# CW308T_MSP430FR5_micro.net
KiCad netlist of a schematic drawn in Altium Designer
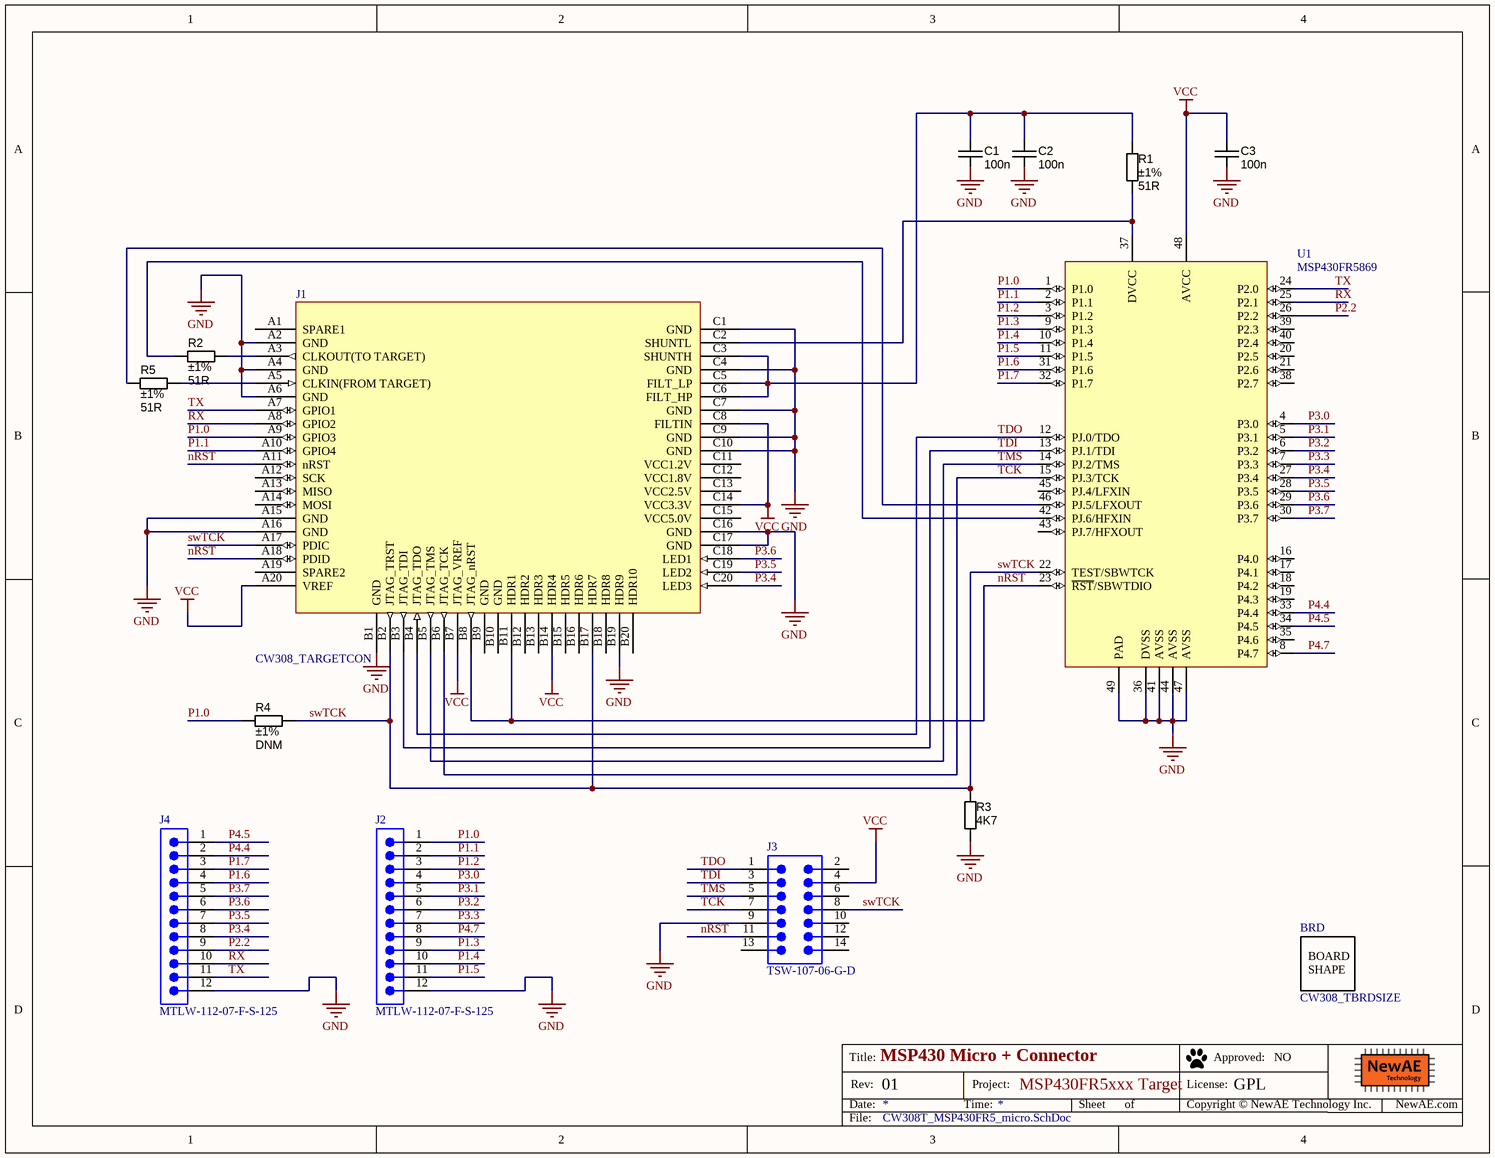
[diagram p0: CW308T_MSP430FR5_micro.SchDoc]

(export (version "E")
  (design (tool "Eeschema 10.0.6"))
  (components
    (comp (ref "BRD")
      (value "CW308_TBRDSIZE")
      (footprint "CW308T_TBOARD_DEFSIZE")
      (description "308T Board Outline (Layer 1)")
      (fields (field (name "PART NUMBER") "CW308T_BRDSHAPE_DEFAULT"))
      (libsource (lib "NewAE_AltiumLib") (part "CW308_TBRDSIZE"))
    )
    (comp (ref "C1")
      (value "100n")
      (footprint "CAPC1608X90N")
      (description "Capacitor SMD Cer 100nF 10% 50V X7R 0603")
      (fields (field (name "TOLERANCE") "±10%") (field (name "Comment") "approved sub OK"))
      (libsource (lib "PBL - Capacitors") (part "CAPC_100n_0603_X7R_50V_10%"))
    )
    (comp (ref "C2")
      (value "100n")
      (footprint "CAPC1608X90N")
      (description "Capacitor SMD Cer 100nF 10% 50V X7R 0603")
      (fields (field (name "TOLERANCE") "±10%") (field (name "Comment") "approved sub OK"))
      (libsource (lib "PBL - Capacitors") (part "CAPC_100n_0603_X7R_50V_10%"))
    )
    (comp (ref "C3")
      (value "100n")
      (footprint "CAPC1608X90N")
      (description "Capacitor SMD Cer 100nF 10% 50V X7R 0603")
      (fields (field (name "TOLERANCE") "±10%") (field (name "Comment") "approved sub OK"))
      (libsource (lib "PBL - Capacitors") (part "CAPC_100n_0603_X7R_50V_10%"))
    )
    (comp (ref "J1")
      (value "CW308_TARGETCON")
      (footprint "ChipWhisperer_AltiumLib:CW308_TBOARD_CONN")
      (description "CW308 \"Standard\" Target Board Connector")
      (libsource (lib "ChipWhisperer_AltiumLib") (part "CW308_TBOARD"))
    )
    (comp (ref "J2")
      (value "MTLW-112-07-F-S-125")
      (footprint "SMTC-MTLW-112-07-X-S-125")
      (fields (field (name "MANUFACTURER") "Samtec"))
      (libsource (lib "Altium Content Vault") (part "SMTC-MTLW-112-07-X-S-125"))
    )
    (comp (ref "J3")
      (value "TSW-107-06-G-D")
      (footprint "SMTC-TSW-107-06-X-D")
      (fields (field (name "MANUFACTURER") "Samtec"))
      (libsource (lib "Altium Content Vault") (part "SMTC-TSW-107-X-X-D-X"))
    )
    (comp (ref "J4")
      (value "MTLW-112-07-F-S-125")
      (footprint "SMTC-MTLW-112-07-X-S-125")
      (fields (field (name "MANUFACTURER") "Samtec"))
      (libsource (lib "Altium Content Vault") (part "SMTC-MTLW-112-07-X-S-125"))
    )
    (comp (ref "R1")
      (value "51R")
      (footprint "RESC1608X55N")
      (description "Resistor SMD chip 51 Ohm 0.1W 1% 0603")
      (fields (field (name "TOLERANCE") "±1%") (field (name "Comment") "Thick Film"))
      (libsource (lib "PBL - Resistors") (part "RES_51R_0603_1%"))
    )
    (comp (ref "R2")
      (value "51R")
      (footprint "RESC1608X55N")
      (description "Resistor SMD chip 51 Ohm 0.1W 1% 0603")
      (fields (field (name "TOLERANCE") "±1%") (field (name "Comment") "Thick Film"))
      (libsource (lib "") (part "RES_51R_0603_1%_1"))
    )
    (comp (ref "R3")
      (value "4K7")
      (footprint "RESC1608X55N")
      (description "Resistor SMD chip 4.7k Ohm 0.1W 5% 0603")
      (fields (field (name "TOLERANCE") "±5%") (field (name "Comment") "Thick Film"))
      (libsource (lib "PBL - Resistors") (part "RES_4K7_0603_5%"))
    )
    (comp (ref "R4")
      (value "DNM")
      (footprint "RESC1608X55N")
      (description "Resistor SMD chip 51 Ohm 0.1W 1% 0603")
      (fields (field (name "TOLERANCE") "±1%") (field (name "Comment") "Thick Film"))
      (libsource (lib "") (part "RES_51R_0603_1%_1"))
    )
    (comp (ref "R5")
      (value "51R")
      (footprint "RESC1608X55N")
      (description "Resistor SMD chip 51 Ohm 0.1W 1% 0603")
      (fields (field (name "TOLERANCE") "±1%") (field (name "Comment") "Thick Film"))
      (libsource (lib "") (part "RES_51R_0603_1%_1"))
    )
    (comp (ref "U1")
      (value "MSP430FR5869")
      (footprint "NewAE_AltiumLib:QFN50P700X700X100_HS-49M")
      (description "MSP430, 16-bit MCU, FR sram")
      (libsource (lib "NewAE_AltiumLib") (part "MSP430FR869"))
    )
  )
  (nets
    (net (code "1") (name "/P1.0") (class "Default")
      (node (ref "J1") (pin "A9") (pinfunction "GPIO3_A9") (pintype "bidirectional"))
      (node (ref "J2") (pin "1") (pinfunction "1_1") (pintype "passive"))
      (node (ref "R4") (pin "1") (pinfunction "1_1") (pintype "passive"))
      (node (ref "U1") (pin "1") (pinfunction "P1.0_1") (pintype "bidirectional"))
    )
    (net (code "2") (name "/P1.1") (class "Default")
      (node (ref "J1") (pin "A10") (pinfunction "GPIO4_A10") (pintype "bidirectional"))
      (node (ref "J2") (pin "2") (pinfunction "2_2") (pintype "passive"))
      (node (ref "U1") (pin "2") (pinfunction "P1.1_2") (pintype "bidirectional"))
    )
    (net (code "3") (name "/P1.2") (class "Default")
      (node (ref "J2") (pin "3") (pinfunction "3_3") (pintype "passive"))
      (node (ref "U1") (pin "3") (pinfunction "P1.2_3") (pintype "bidirectional"))
    )
    (net (code "4") (name "/P1.3") (class "Default")
      (node (ref "J2") (pin "9") (pinfunction "9_9") (pintype "passive"))
      (node (ref "U1") (pin "9") (pinfunction "P1.3_9") (pintype "bidirectional"))
    )
    (net (code "5") (name "/P1.4") (class "Default")
      (node (ref "J2") (pin "10") (pinfunction "10_10") (pintype "passive"))
      (node (ref "U1") (pin "10") (pinfunction "P1.4_10") (pintype "bidirectional"))
    )
    (net (code "6") (name "/P1.5") (class "Default")
      (node (ref "J2") (pin "11") (pinfunction "11_11") (pintype "passive"))
      (node (ref "U1") (pin "11") (pinfunction "P1.5_11") (pintype "bidirectional"))
    )
    (net (code "7") (name "/P1.6") (class "Default")
      (node (ref "J4") (pin "4") (pinfunction "4_4") (pintype "passive"))
      (node (ref "U1") (pin "31") (pinfunction "P1.6_31") (pintype "bidirectional"))
    )
    (net (code "8") (name "/P1.7") (class "Default")
      (node (ref "J4") (pin "3") (pinfunction "3_3") (pintype "passive"))
      (node (ref "U1") (pin "32") (pinfunction "P1.7_32") (pintype "bidirectional"))
    )
    (net (code "9") (name "/P2.2") (class "Default")
      (node (ref "J4") (pin "9") (pinfunction "9_9") (pintype "passive"))
      (node (ref "U1") (pin "26") (pinfunction "P2.2_26") (pintype "bidirectional"))
    )
    (net (code "10") (name "/P3.0") (class "Default")
      (node (ref "J2") (pin "4") (pinfunction "4_4") (pintype "passive"))
      (node (ref "U1") (pin "4") (pinfunction "P3.0_4") (pintype "bidirectional"))
    )
    (net (code "11") (name "/P3.1") (class "Default")
      (node (ref "J2") (pin "5") (pinfunction "5_5") (pintype "passive"))
      (node (ref "U1") (pin "5") (pinfunction "P3.1_5") (pintype "bidirectional"))
    )
    (net (code "12") (name "/P3.2") (class "Default")
      (node (ref "J2") (pin "6") (pinfunction "6_6") (pintype "passive"))
      (node (ref "U1") (pin "6") (pinfunction "P3.2_6") (pintype "bidirectional"))
    )
    (net (code "13") (name "/P3.3") (class "Default")
      (node (ref "J2") (pin "7") (pinfunction "7_7") (pintype "passive"))
      (node (ref "U1") (pin "7") (pinfunction "P3.3_7") (pintype "bidirectional"))
    )
    (net (code "14") (name "/P3.4") (class "Default")
      (node (ref "J1") (pin "C20") (pinfunction "LED3_C20") (pintype "input"))
      (node (ref "J4") (pin "8") (pinfunction "8_8") (pintype "passive"))
      (node (ref "U1") (pin "27") (pinfunction "P3.4_27") (pintype "bidirectional"))
    )
    (net (code "15") (name "/P3.5") (class "Default")
      (node (ref "J1") (pin "C19") (pinfunction "LED2_C19") (pintype "input"))
      (node (ref "J4") (pin "7") (pinfunction "7_7") (pintype "passive"))
      (node (ref "U1") (pin "28") (pinfunction "P3.5_28") (pintype "bidirectional"))
    )
    (net (code "16") (name "/P3.6") (class "Default")
      (node (ref "J1") (pin "C18") (pinfunction "LED1_C18") (pintype "input"))
      (node (ref "J4") (pin "6") (pinfunction "6_6") (pintype "passive"))
      (node (ref "U1") (pin "29") (pinfunction "P3.6_29") (pintype "bidirectional"))
    )
    (net (code "17") (name "/P3.7") (class "Default")
      (node (ref "J4") (pin "5") (pinfunction "5_5") (pintype "passive"))
      (node (ref "U1") (pin "30") (pinfunction "P3.7_30") (pintype "bidirectional"))
    )
    (net (code "18") (name "/P4.4") (class "Default")
      (node (ref "J4") (pin "2") (pinfunction "2_2") (pintype "passive"))
      (node (ref "U1") (pin "33") (pinfunction "P4.4_33") (pintype "bidirectional"))
    )
    (net (code "19") (name "/P4.5") (class "Default")
      (node (ref "J4") (pin "1") (pinfunction "1_1") (pintype "passive"))
      (node (ref "U1") (pin "34") (pinfunction "P4.5_34") (pintype "bidirectional"))
    )
    (net (code "20") (name "/P4.7") (class "Default")
      (node (ref "J2") (pin "8") (pinfunction "8_8") (pintype "passive"))
      (node (ref "U1") (pin "8") (pinfunction "P4.7_8") (pintype "bidirectional"))
    )
    (net (code "21") (name "/RX") (class "Default")
      (node (ref "J1") (pin "A8") (pinfunction "GPIO2_A8") (pintype "bidirectional"))
      (node (ref "J4") (pin "10") (pinfunction "10_10") (pintype "passive"))
      (node (ref "U1") (pin "25") (pinfunction "P2.1_25") (pintype "bidirectional"))
    )
    (net (code "22") (name "/TCK") (class "Default")
      (node (ref "J1") (pin "B6") (pinfunction "JTAG_TCK_B6") (pintype "output"))
      (node (ref "J3") (pin "7") (pinfunction "7_7") (pintype "passive"))
      (node (ref "U1") (pin "15") (pinfunction "PJ.3/TCK_15") (pintype "bidirectional"))
    )
    (net (code "23") (name "/TDI") (class "Default")
      (node (ref "J1") (pin "B3") (pinfunction "JTAG_TDI_B3") (pintype "output"))
      (node (ref "J3") (pin "3") (pinfunction "3_3") (pintype "passive"))
      (node (ref "U1") (pin "13") (pinfunction "PJ.1/TDI_13") (pintype "bidirectional"))
    )
    (net (code "24") (name "/TDO") (class "Default")
      (node (ref "J1") (pin "B4") (pinfunction "JTAG_TDO_B4") (pintype "input"))
      (node (ref "J3") (pin "1") (pinfunction "1_1") (pintype "passive"))
      (node (ref "U1") (pin "12") (pinfunction "PJ.0/TDO_12") (pintype "bidirectional"))
    )
    (net (code "25") (name "/TMS") (class "Default")
      (node (ref "J1") (pin "B5") (pinfunction "JTAG_TMS_B5") (pintype "output"))
      (node (ref "J3") (pin "5") (pinfunction "5_5") (pintype "passive"))
      (node (ref "U1") (pin "14") (pinfunction "PJ.2/TMS_14") (pintype "bidirectional"))
    )
    (net (code "26") (name "/TX") (class "Default")
      (node (ref "J1") (pin "A7") (pinfunction "GPIO1_A7") (pintype "bidirectional"))
      (node (ref "J4") (pin "11") (pinfunction "11_11") (pintype "passive"))
      (node (ref "U1") (pin "24") (pinfunction "P2.0_24") (pintype "bidirectional"))
    )
    (net (code "27") (name "/nRST") (class "Default")
      (node (ref "J1") (pin "A11") (pinfunction "nRST_A11") (pintype "bidirectional"))
      (node (ref "J1") (pin "A18") (pinfunction "PDID_A18") (pintype "bidirectional"))
      (node (ref "J1") (pin "B11") (pinfunction "HDR1_B11") (pintype "passive"))
      (node (ref "J1") (pin "B8") (pinfunction "JTAG_nRST_B8") (pintype "output"))
      (node (ref "J3") (pin "11") (pinfunction "11_11") (pintype "passive"))
      (node (ref "U1") (pin "23") (pinfunction "~{RST}/SBWTDIO_23") (pintype "bidirectional"))
    )
    (net (code "28") (name "/swTCK") (class "Default")
      (node (ref "J1") (pin "A17") (pinfunction "PDIC_A17") (pintype "bidirectional"))
      (node (ref "J1") (pin "B17") (pinfunction "HDR7_B17") (pintype "passive"))
      (node (ref "J1") (pin "B2") (pinfunction "JTAG_TRST_B2") (pintype "output"))
      (node (ref "J3") (pin "8") (pinfunction "8_8") (pintype "passive"))
      (node (ref "R3") (pin "1") (pinfunction "1_1") (pintype "passive"))
      (node (ref "R4") (pin "2") (pinfunction "2_2") (pintype "passive"))
      (node (ref "U1") (pin "22") (pinfunction "TEST/SBWTCK_22") (pintype "bidirectional"))
    )
    (net (code "29") (name "GND") (class "Default")
      (node (ref "C1") (pin "2") (pintype "passive"))
      (node (ref "C2") (pin "2") (pintype "passive"))
      (node (ref "C3") (pin "2") (pintype "passive"))
      (node (ref "J1") (pin "A15") (pinfunction "GND_A15") (pintype "passive"))
      (node (ref "J1") (pin "A16") (pinfunction "GND_A16") (pintype "passive"))
      (node (ref "J1") (pin "A2") (pinfunction "GND_A2") (pintype "passive"))
      (node (ref "J1") (pin "A4") (pinfunction "GND_A4") (pintype "passive"))
      (node (ref "J1") (pin "A6") (pinfunction "GND_A6") (pintype "power_in"))
      (node (ref "J1") (pin "B1") (pinfunction "GND_B1") (pintype "passive"))
      (node (ref "J1") (pin "B19") (pinfunction "HDR9_B19") (pintype "passive"))
      (node (ref "J1") (pin "C1") (pinfunction "GND_C1") (pintype "power_in"))
      (node (ref "J1") (pin "C10") (pinfunction "GND_C10") (pintype "power_in"))
      (node (ref "J1") (pin "C16") (pinfunction "GND_C16") (pintype "power_in"))
      (node (ref "J1") (pin "C17") (pinfunction "GND_C17") (pintype "power_in"))
      (node (ref "J1") (pin "C4") (pinfunction "GND_C4") (pintype "power_in"))
      (node (ref "J1") (pin "C7") (pinfunction "GND_C7") (pintype "power_in"))
      (node (ref "J1") (pin "C9") (pinfunction "GND_C9") (pintype "power_in"))
      (node (ref "J2") (pin "12") (pinfunction "12_12") (pintype "passive"))
      (node (ref "J3") (pin "9") (pinfunction "9_9") (pintype "passive"))
      (node (ref "J4") (pin "12") (pinfunction "12_12") (pintype "passive"))
      (node (ref "R3") (pin "2") (pinfunction "2_2") (pintype "passive"))
      (node (ref "U1") (pin "36") (pinfunction "DVSS_36") (pintype "power_in"))
      (node (ref "U1") (pin "41") (pinfunction "AVSS_41") (pintype "power_in"))
      (node (ref "U1") (pin "44") (pinfunction "AVSS_44") (pintype "power_in"))
      (node (ref "U1") (pin "47") (pinfunction "AVSS_47") (pintype "power_in"))
      (node (ref "U1") (pin "49") (pinfunction "PAD_49") (pintype "power_in"))
    )
    (net (code "30") (name "Net-(J1-CLKIN(FROM_TARGET))") (class "Default")
      (node (ref "J1") (pin "A5") (pinfunction "CLKIN(FROM_TARGET)_A5") (pintype "input"))
      (node (ref "R5") (pin "2") (pinfunction "2_2") (pintype "passive"))
    )
    (net (code "31") (name "Net-(J1-CLKOUT(TO_TARGET))") (class "Default")
      (node (ref "J1") (pin "A3") (pinfunction "CLKOUT(TO_TARGET)_A3") (pintype "output"))
      (node (ref "R2") (pin "2") (pinfunction "2_2") (pintype "passive"))
    )
    (net (code "32") (name "Net-(J1-FILT_HP)") (class "Default")
      (node (ref "C1") (pin "1") (pintype "passive"))
      (node (ref "C2") (pin "1") (pintype "passive"))
      (node (ref "J1") (pin "C3") (pinfunction "SHUNTH_C3") (pintype "passive"))
      (node (ref "J1") (pin "C5") (pinfunction "FILT_LP_C5") (pintype "passive"))
      (node (ref "J1") (pin "C6") (pinfunction "FILT_HP_C6") (pintype "passive"))
      (node (ref "R1") (pin "1") (pinfunction "1_1") (pintype "passive"))
    )
    (net (code "33") (name "Net-(J1-SHUNTL)") (class "Default")
      (node (ref "J1") (pin "C2") (pinfunction "SHUNTL_C2") (pintype "passive"))
      (node (ref "R1") (pin "2") (pinfunction "2_2") (pintype "passive"))
      (node (ref "U1") (pin "37") (pinfunction "DVCC_37") (pintype "power_in"))
    )
    (net (code "34") (name "Net-(U1-PJ.5{slash}LFXOUT)") (class "Default")
      (node (ref "R5") (pin "1") (pinfunction "1_1") (pintype "passive"))
      (node (ref "U1") (pin "46") (pinfunction "PJ.5/LFXOUT_46") (pintype "bidirectional"))
    )
    (net (code "35") (name "Net-(U1-PJ.6{slash}HFXIN)") (class "Default")
      (node (ref "R2") (pin "1") (pinfunction "1_1") (pintype "passive"))
      (node (ref "U1") (pin "42") (pinfunction "PJ.6/HFXIN_42") (pintype "bidirectional"))
    )
    (net (code "36") (name "VCC") (class "Default")
      (node (ref "C3") (pin "1") (pintype "passive"))
      (node (ref "J1") (pin "A20") (pinfunction "VREF_A20") (pintype "tri_state"))
      (node (ref "J1") (pin "B14") (pinfunction "HDR4_B14") (pintype "passive"))
      (node (ref "J1") (pin "B7") (pinfunction "JTAG_VREF_B7") (pintype "tri_state"))
      (node (ref "J1") (pin "C14") (pinfunction "VCC3.3V_C14") (pintype "power_in"))
      (node (ref "J1") (pin "C8") (pinfunction "FILTIN_C8") (pintype "passive"))
      (node (ref "J3") (pin "4") (pinfunction "4_4") (pintype "passive"))
      (node (ref "U1") (pin "48") (pinfunction "AVCC_48") (pintype "power_in"))
    )
    (net (code "37") (name "unconnected-(J1-GND-PadB9)") (class "Default")
      (node (ref "J1") (pin "B9") (pinfunction "GND_B9") (pintype "passive"))
    )
    (net (code "38") (name "unconnected-(J1-GND-PadB10)") (class "Default")
      (node (ref "J1") (pin "B10") (pinfunction "GND_B10") (pintype "passive"))
    )
    (net (code "39") (name "unconnected-(J1-HDR2-PadB12)") (class "Default")
      (node (ref "J1") (pin "B12") (pinfunction "HDR2_B12") (pintype "passive"))
    )
    (net (code "40") (name "unconnected-(J1-HDR3-PadB13)") (class "Default")
      (node (ref "J1") (pin "B13") (pinfunction "HDR3_B13") (pintype "passive"))
    )
    (net (code "41") (name "unconnected-(J1-HDR5-PadB15)") (class "Default")
      (node (ref "J1") (pin "B15") (pinfunction "HDR5_B15") (pintype "passive"))
    )
    (net (code "42") (name "unconnected-(J1-HDR6-PadB16)") (class "Default")
      (node (ref "J1") (pin "B16") (pinfunction "HDR6_B16") (pintype "passive"))
    )
    (net (code "43") (name "unconnected-(J1-HDR8-PadB18)") (class "Default")
      (node (ref "J1") (pin "B18") (pinfunction "HDR8_B18") (pintype "passive"))
    )
    (net (code "44") (name "unconnected-(J1-HDR10-PadB20)") (class "Default")
      (node (ref "J1") (pin "B20") (pinfunction "HDR10_B20") (pintype "passive"))
    )
    (net (code "45") (name "unconnected-(J1-MISO-PadA13)") (class "Default")
      (node (ref "J1") (pin "A13") (pinfunction "MISO_A13") (pintype "bidirectional"))
    )
    (net (code "46") (name "unconnected-(J1-MOSI-PadA14)") (class "Default")
      (node (ref "J1") (pin "A14") (pinfunction "MOSI_A14") (pintype "bidirectional"))
    )
    (net (code "47") (name "unconnected-(J1-SCK-PadA12)") (class "Default")
      (node (ref "J1") (pin "A12") (pinfunction "SCK_A12") (pintype "bidirectional"))
    )
    (net (code "48") (name "unconnected-(J1-SPARE1-PadA1)") (class "Default")
      (node (ref "J1") (pin "A1") (pinfunction "SPARE1_A1") (pintype "passive"))
    )
    (net (code "49") (name "unconnected-(J1-SPARE2-PadA19)") (class "Default")
      (node (ref "J1") (pin "A19") (pinfunction "SPARE2_A19") (pintype "passive"))
    )
    (net (code "50") (name "unconnected-(J1-VCC1.2V-PadC11)") (class "Default")
      (node (ref "J1") (pin "C11") (pinfunction "VCC1.2V_C11") (pintype "power_in"))
    )
    (net (code "51") (name "unconnected-(J1-VCC1.8V-PadC12)") (class "Default")
      (node (ref "J1") (pin "C12") (pinfunction "VCC1.8V_C12") (pintype "power_in"))
    )
    (net (code "52") (name "unconnected-(J1-VCC2.5V-PadC13)") (class "Default")
      (node (ref "J1") (pin "C13") (pinfunction "VCC2.5V_C13") (pintype "power_in"))
    )
    (net (code "53") (name "unconnected-(J1-VCC5.0V-PadC15)") (class "Default")
      (node (ref "J1") (pin "C15") (pinfunction "VCC5.0V_C15") (pintype "power_in"))
    )
    (net (code "54") (name "unconnected-(J3-Pad2)") (class "Default")
      (node (ref "J3") (pin "2") (pinfunction "2_2") (pintype "passive"))
    )
    (net (code "55") (name "unconnected-(J3-Pad6)") (class "Default")
      (node (ref "J3") (pin "6") (pinfunction "6_6") (pintype "passive"))
    )
    (net (code "56") (name "unconnected-(J3-Pad10)") (class "Default")
      (node (ref "J3") (pin "10") (pinfunction "10_10") (pintype "passive"))
    )
    (net (code "57") (name "unconnected-(J3-Pad12)") (class "Default")
      (node (ref "J3") (pin "12") (pinfunction "12_12") (pintype "passive"))
    )
    (net (code "58") (name "unconnected-(J3-Pad13)") (class "Default")
      (node (ref "J3") (pin "13") (pinfunction "13_13") (pintype "passive"))
    )
    (net (code "59") (name "unconnected-(J3-Pad14)") (class "Default")
      (node (ref "J3") (pin "14") (pinfunction "14_14") (pintype "passive"))
    )
    (net (code "60") (name "unconnected-(U1-P2.3-Pad39)") (class "Default")
      (node (ref "U1") (pin "39") (pinfunction "P2.3_39") (pintype "bidirectional"))
    )
    (net (code "61") (name "unconnected-(U1-P2.4-Pad40)") (class "Default")
      (node (ref "U1") (pin "40") (pinfunction "P2.4_40") (pintype "bidirectional"))
    )
    (net (code "62") (name "unconnected-(U1-P2.5-Pad20)") (class "Default")
      (node (ref "U1") (pin "20") (pinfunction "P2.5_20") (pintype "bidirectional"))
    )
    (net (code "63") (name "unconnected-(U1-P2.6-Pad21)") (class "Default")
      (node (ref "U1") (pin "21") (pinfunction "P2.6_21") (pintype "bidirectional"))
    )
    (net (code "64") (name "unconnected-(U1-P2.7-Pad38)") (class "Default")
      (node (ref "U1") (pin "38") (pinfunction "P2.7_38") (pintype "bidirectional"))
    )
    (net (code "65") (name "unconnected-(U1-P4.0-Pad16)") (class "Default")
      (node (ref "U1") (pin "16") (pinfunction "P4.0_16") (pintype "bidirectional"))
    )
    (net (code "66") (name "unconnected-(U1-P4.1-Pad17)") (class "Default")
      (node (ref "U1") (pin "17") (pinfunction "P4.1_17") (pintype "bidirectional"))
    )
    (net (code "67") (name "unconnected-(U1-P4.2-Pad18)") (class "Default")
      (node (ref "U1") (pin "18") (pinfunction "P4.2_18") (pintype "bidirectional"))
    )
    (net (code "68") (name "unconnected-(U1-P4.3-Pad19)") (class "Default")
      (node (ref "U1") (pin "19") (pinfunction "P4.3_19") (pintype "bidirectional"))
    )
    (net (code "69") (name "unconnected-(U1-P4.6-Pad35)") (class "Default")
      (node (ref "U1") (pin "35") (pinfunction "P4.6_35") (pintype "bidirectional"))
    )
    (net (code "70") (name "unconnected-(U1-PJ.4{slash}LFXIN-Pad45)") (class "Default")
      (node (ref "U1") (pin "45") (pinfunction "PJ.4/LFXIN_45") (pintype "bidirectional"))
    )
    (net (code "71") (name "unconnected-(U1-PJ.7{slash}HFXOUT-Pad43)") (class "Default")
      (node (ref "U1") (pin "43") (pinfunction "PJ.7/HFXOUT_43") (pintype "bidirectional"))
    )
  )
)
